# Hori_Dpad.net
KiCad netlist of a schematic drawn in EAGLE
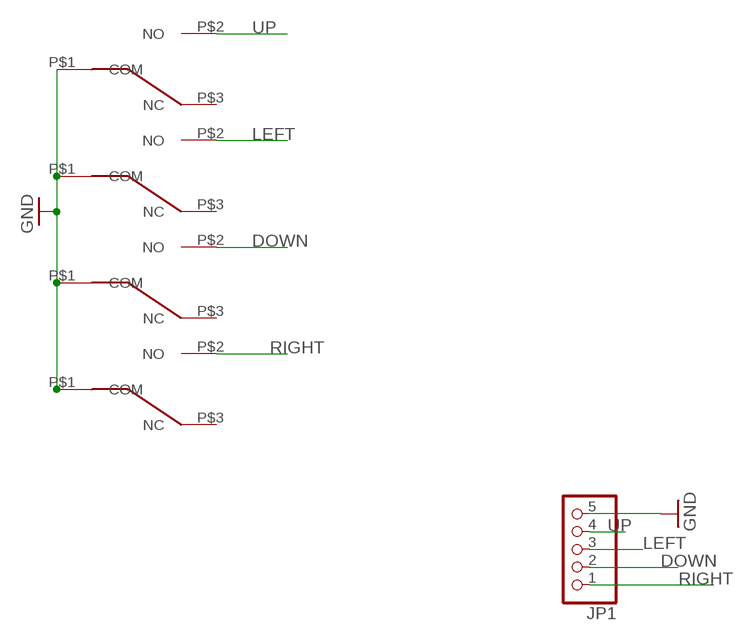
[diagram p0: schematic, sheet 1]

(export (version "E")
  (design (tool "Eeschema 10.0.6"))
  (components
    (comp (ref "DOWN")
      (value "OMRON_D2FC-F-7N")
      (footprint "eagle-import:D2FC-F-K")
      (libsource (lib "eagle-import") (part "OMRON_D2FC-F-7N"))
    )
    (comp (ref "JP1")
      (value "PINHD-1X05_2.00")
      (footprint "eagle-import:1X05M")
      (libsource (lib "eagle-import") (part "PINHD-1X05_2.00"))
    )
    (comp (ref "LEFT")
      (value "OMRON_D2FC-F-7N")
      (footprint "eagle-import:D2FC-F-K")
      (libsource (lib "eagle-import") (part "OMRON_D2FC-F-7N"))
    )
    (comp (ref "RIGHT")
      (value "OMRON_D2FC-F-7N")
      (footprint "eagle-import:D2FC-F-K")
      (libsource (lib "eagle-import") (part "OMRON_D2FC-F-7N"))
    )
    (comp (ref "UP")
      (value "OMRON_D2FC-F-7N")
      (footprint "eagle-import:D2FC-F-K")
      (libsource (lib "eagle-import") (part "OMRON_D2FC-F-7N"))
    )
  )
  (nets
    (net (code "1") (name "/DOWN") (class "Default")
      (node (ref "DOWN") (pin "P$2") (pinfunction "NO_P$2") (pintype "bidirectional"))
      (node (ref "JP1") (pin "2") (pinfunction "2_2") (pintype "passive"))
    )
    (net (code "2") (name "/LEFT") (class "Default")
      (node (ref "JP1") (pin "3") (pinfunction "3_3") (pintype "passive"))
      (node (ref "LEFT") (pin "P$2") (pinfunction "NO_P$2") (pintype "bidirectional"))
    )
    (net (code "3") (name "/RIGHT") (class "Default")
      (node (ref "JP1") (pin "1") (pinfunction "1_1") (pintype "passive"))
      (node (ref "RIGHT") (pin "P$2") (pinfunction "NO_P$2") (pintype "bidirectional"))
    )
    (net (code "4") (name "/UP") (class "Default")
      (node (ref "JP1") (pin "4") (pinfunction "4_4") (pintype "passive"))
      (node (ref "UP") (pin "P$2") (pinfunction "NO_P$2") (pintype "bidirectional"))
    )
    (net (code "5") (name "GND") (class "Default")
      (node (ref "DOWN") (pin "P$1") (pinfunction "COM_P$1") (pintype "bidirectional"))
      (node (ref "JP1") (pin "5") (pinfunction "5_5") (pintype "passive"))
      (node (ref "LEFT") (pin "P$1") (pinfunction "COM_P$1") (pintype "bidirectional"))
      (node (ref "RIGHT") (pin "P$1") (pinfunction "COM_P$1") (pintype "bidirectional"))
      (node (ref "UP") (pin "P$1") (pinfunction "COM_P$1") (pintype "bidirectional"))
    )
    (net (code "6") (name "unconnected-(DOWN-NC-PadP$3)") (class "Default")
      (node (ref "DOWN") (pin "P$3") (pinfunction "NC_P$3") (pintype "bidirectional"))
    )
    (net (code "7") (name "unconnected-(LEFT-NC-PadP$3)") (class "Default")
      (node (ref "LEFT") (pin "P$3") (pinfunction "NC_P$3") (pintype "bidirectional"))
    )
    (net (code "8") (name "unconnected-(RIGHT-NC-PadP$3)") (class "Default")
      (node (ref "RIGHT") (pin "P$3") (pinfunction "NC_P$3") (pintype "bidirectional"))
    )
    (net (code "9") (name "unconnected-(UP-NC-PadP$3)") (class "Default")
      (node (ref "UP") (pin "P$3") (pinfunction "NC_P$3") (pintype "bidirectional"))
    )
  )
)
